# Callisto_Teknic_MSOx4_LSx3_v1p0.net
KiCad netlist of a schematic drawn in EAGLE
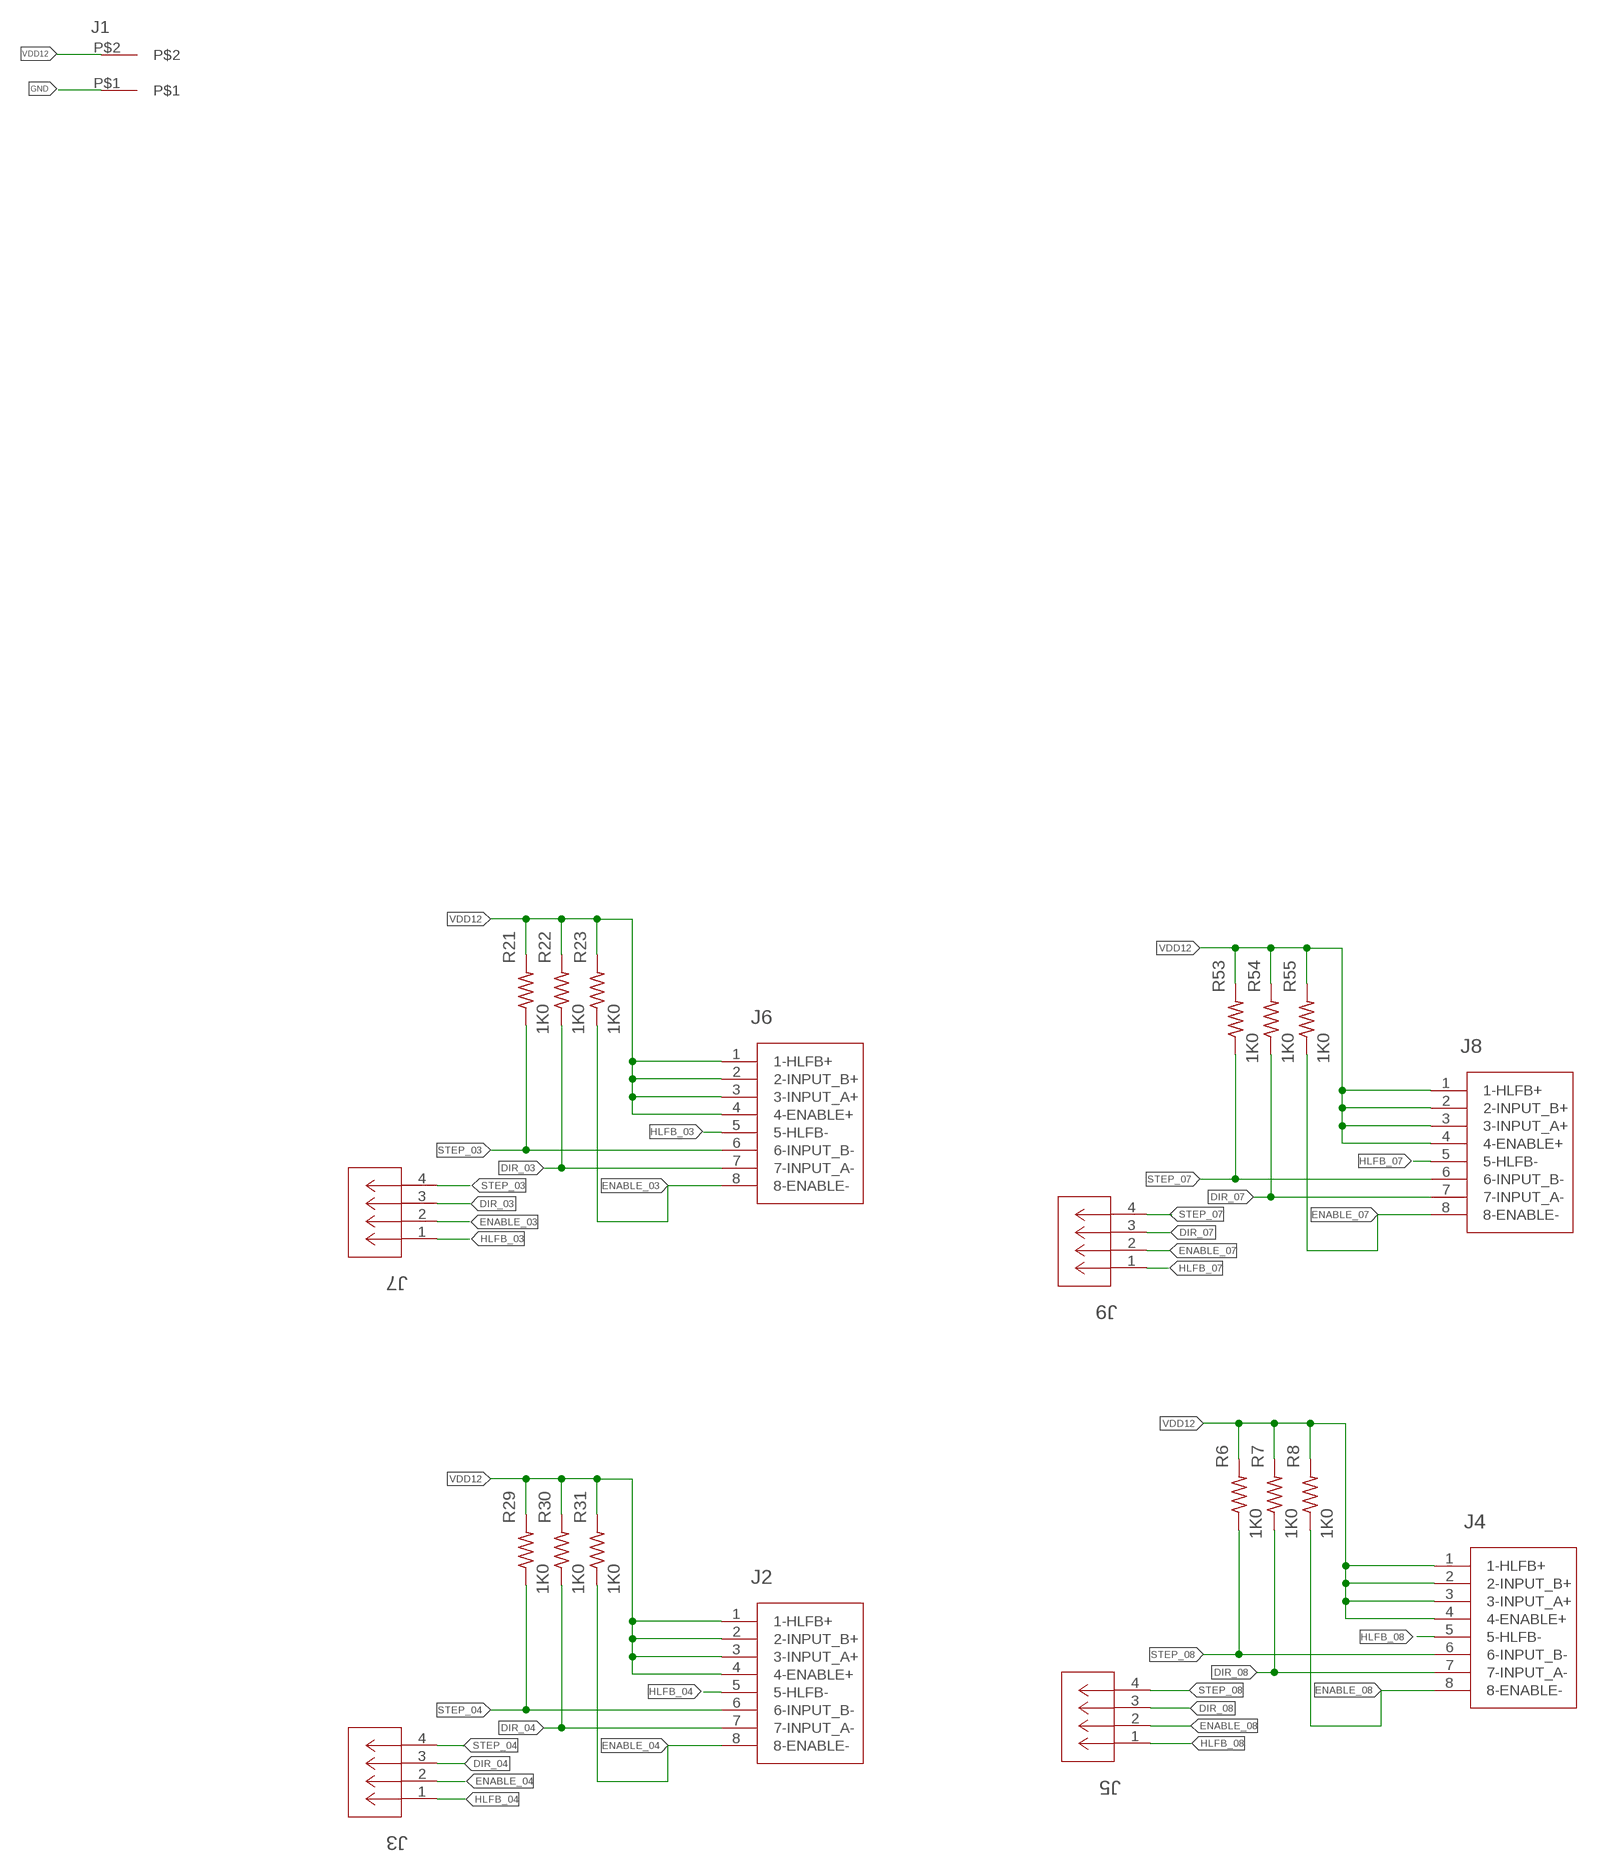
[diagram p0: schematic, sheet 1]

(export (version "E")
  (design (tool "Eeschema 10.0.6"))
  (components
    (comp (ref "J1")
      (value "2-pos")
      (footprint "eagle-import:2_3.81MM_PITCH")
      (fields (field (name "PARTNO") "691322310002"))
      (libsource (lib "eagle-import") (part "3.81MM_1_X_2_RT_ANGLE_PLUG_HEADER"))
    )
    (comp (ref "J2")
      (value "TEKNIC_8PIN_MOTOR")
      (footprint "eagle-import:CON_39281083")
      (fields
        (field (name "MANUFACTURER_PART_NUMBER") "39281083")
        (field (name "COPYRIGHT") "Copyright (C) 2022 Ultra Librarian. All rights reserved.")
      )
      (libsource (lib "eagle-import") (part "TEKNIC_8PIN_MOTOR"))
    )
    (comp (ref "J3")
      (value "CONN_530470410_PICOBLADE_X_4")
      (footprint "eagle-import:CON_530470410_MOL")
      (fields
        (field (name "MANUFACTURER_PART_NUMBER") "530470410")
        (field (name "COPYRIGHT") "Copyright (C) 2022 Ultra Librarian. All rights reserved.")
      )
      (libsource (lib "eagle-import") (part "CONN_530470410_PICOBLADE_X_4"))
    )
    (comp (ref "J4")
      (value "TEKNIC_8PIN_MOTOR")
      (footprint "eagle-import:CON_39281083")
      (fields
        (field (name "MANUFACTURER_PART_NUMBER") "39281083")
        (field (name "COPYRIGHT") "Copyright (C) 2022 Ultra Librarian. All rights reserved.")
      )
      (libsource (lib "eagle-import") (part "TEKNIC_8PIN_MOTOR"))
    )
    (comp (ref "J5")
      (value "CONN_530470410_PICOBLADE_X_4")
      (footprint "eagle-import:CON_530470410_MOL")
      (fields
        (field (name "MANUFACTURER_PART_NUMBER") "530470410")
        (field (name "COPYRIGHT") "Copyright (C) 2022 Ultra Librarian. All rights reserved.")
      )
      (libsource (lib "eagle-import") (part "CONN_530470410_PICOBLADE_X_4"))
    )
    (comp (ref "J6")
      (value "TEKNIC_8PIN_MOTOR")
      (footprint "eagle-import:CON_39281083")
      (fields
        (field (name "MANUFACTURER_PART_NUMBER") "39281083")
        (field (name "COPYRIGHT") "Copyright (C) 2022 Ultra Librarian. All rights reserved.")
      )
      (libsource (lib "eagle-import") (part "TEKNIC_8PIN_MOTOR"))
    )
    (comp (ref "J7")
      (value "CONN_530470410_PICOBLADE_X_4")
      (footprint "eagle-import:CON_530470410_MOL")
      (fields
        (field (name "MANUFACTURER_PART_NUMBER") "530470410")
        (field (name "COPYRIGHT") "Copyright (C) 2022 Ultra Librarian. All rights reserved.")
      )
      (libsource (lib "eagle-import") (part "CONN_530470410_PICOBLADE_X_4"))
    )
    (comp (ref "J8")
      (value "TEKNIC_8PIN_MOTOR")
      (footprint "eagle-import:CON_39281083")
      (fields
        (field (name "MANUFACTURER_PART_NUMBER") "39281083")
        (field (name "COPYRIGHT") "Copyright (C) 2022 Ultra Librarian. All rights reserved.")
      )
      (libsource (lib "eagle-import") (part "TEKNIC_8PIN_MOTOR"))
    )
    (comp (ref "J9")
      (value "CONN_530470410_PICOBLADE_X_4")
      (footprint "eagle-import:CON_530470410_MOL")
      (fields
        (field (name "MANUFACTURER_PART_NUMBER") "530470410")
        (field (name "COPYRIGHT") "Copyright (C) 2022 Ultra Librarian. All rights reserved.")
      )
      (libsource (lib "eagle-import") (part "CONN_530470410_PICOBLADE_X_4"))
    )
    (comp (ref "R6")
      (value "1K0")
      (footprint "eagle-import:0402")
      (fields (field (name "PARTNO") "CRG0402J1K0"))
      (libsource (lib "eagle-import") (part "R_0402_1K0"))
    )
    (comp (ref "R7")
      (value "1K0")
      (footprint "eagle-import:0402")
      (fields (field (name "PARTNO") "CRG0402J1K0"))
      (libsource (lib "eagle-import") (part "R_0402_1K0"))
    )
    (comp (ref "R8")
      (value "1K0")
      (footprint "eagle-import:0402")
      (fields (field (name "PARTNO") "CRG0402J1K0"))
      (libsource (lib "eagle-import") (part "R_0402_1K0"))
    )
    (comp (ref "R21")
      (value "1K0")
      (footprint "eagle-import:0402")
      (fields (field (name "PARTNO") "CRG0402J1K0"))
      (libsource (lib "eagle-import") (part "R_0402_1K0"))
    )
    (comp (ref "R22")
      (value "1K0")
      (footprint "eagle-import:0402")
      (fields (field (name "PARTNO") "CRG0402J1K0"))
      (libsource (lib "eagle-import") (part "R_0402_1K0"))
    )
    (comp (ref "R23")
      (value "1K0")
      (footprint "eagle-import:0402")
      (fields (field (name "PARTNO") "CRG0402J1K0"))
      (libsource (lib "eagle-import") (part "R_0402_1K0"))
    )
    (comp (ref "R29")
      (value "1K0")
      (footprint "eagle-import:0402")
      (fields (field (name "PARTNO") "CRG0402J1K0"))
      (libsource (lib "eagle-import") (part "R_0402_1K0"))
    )
    (comp (ref "R30")
      (value "1K0")
      (footprint "eagle-import:0402")
      (fields (field (name "PARTNO") "CRG0402J1K0"))
      (libsource (lib "eagle-import") (part "R_0402_1K0"))
    )
    (comp (ref "R31")
      (value "1K0")
      (footprint "eagle-import:0402")
      (fields (field (name "PARTNO") "CRG0402J1K0"))
      (libsource (lib "eagle-import") (part "R_0402_1K0"))
    )
    (comp (ref "R53")
      (value "1K0")
      (footprint "eagle-import:0402")
      (fields (field (name "PARTNO") "CRG0402J1K0"))
      (libsource (lib "eagle-import") (part "R_0402_1K0"))
    )
    (comp (ref "R54")
      (value "1K0")
      (footprint "eagle-import:0402")
      (fields (field (name "PARTNO") "CRG0402J1K0"))
      (libsource (lib "eagle-import") (part "R_0402_1K0"))
    )
    (comp (ref "R55")
      (value "1K0")
      (footprint "eagle-import:0402")
      (fields (field (name "PARTNO") "CRG0402J1K0"))
      (libsource (lib "eagle-import") (part "R_0402_1K0"))
    )
  )
  (nets
    (net (code "1") (name "DIR_03") (class "Default")
      (node (ref "J6") (pin "7") (pinfunction "7-INPUT_A-_7") (pintype "passive"))
      (node (ref "J7") (pin "3") (pinfunction "3_3") (pintype "passive"))
      (node (ref "R22") (pin "1") (pinfunction "1_1") (pintype "passive"))
    )
    (net (code "2") (name "DIR_04") (class "Default")
      (node (ref "J2") (pin "7") (pinfunction "7-INPUT_A-_7") (pintype "passive"))
      (node (ref "J3") (pin "3") (pinfunction "3_3") (pintype "passive"))
      (node (ref "R30") (pin "1") (pinfunction "1_1") (pintype "passive"))
    )
    (net (code "3") (name "DIR_07") (class "Default")
      (node (ref "J8") (pin "7") (pinfunction "7-INPUT_A-_7") (pintype "passive"))
      (node (ref "J9") (pin "3") (pinfunction "3_3") (pintype "passive"))
      (node (ref "R54") (pin "1") (pinfunction "1_1") (pintype "passive"))
    )
    (net (code "4") (name "DIR_08") (class "Default")
      (node (ref "J4") (pin "7") (pinfunction "7-INPUT_A-_7") (pintype "passive"))
      (node (ref "J5") (pin "3") (pinfunction "3_3") (pintype "passive"))
      (node (ref "R7") (pin "1") (pinfunction "1_1") (pintype "passive"))
    )
    (net (code "5") (name "ENABLE_03") (class "Default")
      (node (ref "J6") (pin "8") (pinfunction "8-ENABLE-_8") (pintype "passive"))
      (node (ref "J7") (pin "2") (pinfunction "2_2") (pintype "passive"))
      (node (ref "R23") (pin "1") (pinfunction "1_1") (pintype "passive"))
    )
    (net (code "6") (name "ENABLE_04") (class "Default")
      (node (ref "J2") (pin "8") (pinfunction "8-ENABLE-_8") (pintype "passive"))
      (node (ref "J3") (pin "2") (pinfunction "2_2") (pintype "passive"))
      (node (ref "R31") (pin "1") (pinfunction "1_1") (pintype "passive"))
    )
    (net (code "7") (name "ENABLE_07") (class "Default")
      (node (ref "J8") (pin "8") (pinfunction "8-ENABLE-_8") (pintype "passive"))
      (node (ref "J9") (pin "2") (pinfunction "2_2") (pintype "passive"))
      (node (ref "R55") (pin "1") (pinfunction "1_1") (pintype "passive"))
    )
    (net (code "8") (name "ENABLE_08") (class "Default")
      (node (ref "J4") (pin "8") (pinfunction "8-ENABLE-_8") (pintype "passive"))
      (node (ref "J5") (pin "2") (pinfunction "2_2") (pintype "passive"))
      (node (ref "R8") (pin "1") (pinfunction "1_1") (pintype "passive"))
    )
    (net (code "9") (name "GND") (class "Default")
      (node (ref "J1") (pin "P$1") (pinfunction "P$1_P$1") (pintype "bidirectional"))
    )
    (net (code "10") (name "HLFB_03") (class "Default")
      (node (ref "J6") (pin "5") (pinfunction "5-HLFB-_5") (pintype "passive"))
      (node (ref "J7") (pin "1") (pinfunction "1_1") (pintype "passive"))
    )
    (net (code "11") (name "HLFB_04") (class "Default")
      (node (ref "J2") (pin "5") (pinfunction "5-HLFB-_5") (pintype "passive"))
      (node (ref "J3") (pin "1") (pinfunction "1_1") (pintype "passive"))
    )
    (net (code "12") (name "HLFB_07") (class "Default")
      (node (ref "J8") (pin "5") (pinfunction "5-HLFB-_5") (pintype "passive"))
      (node (ref "J9") (pin "1") (pinfunction "1_1") (pintype "passive"))
    )
    (net (code "13") (name "HLFB_08") (class "Default")
      (node (ref "J4") (pin "5") (pinfunction "5-HLFB-_5") (pintype "passive"))
      (node (ref "J5") (pin "1") (pinfunction "1_1") (pintype "passive"))
    )
    (net (code "14") (name "STEP_03") (class "Default")
      (node (ref "J6") (pin "6") (pinfunction "6-INPUT_B-_6") (pintype "passive"))
      (node (ref "J7") (pin "4") (pinfunction "4_4") (pintype "passive"))
      (node (ref "R21") (pin "1") (pinfunction "1_1") (pintype "passive"))
    )
    (net (code "15") (name "STEP_04") (class "Default")
      (node (ref "J2") (pin "6") (pinfunction "6-INPUT_B-_6") (pintype "passive"))
      (node (ref "J3") (pin "4") (pinfunction "4_4") (pintype "passive"))
      (node (ref "R29") (pin "1") (pinfunction "1_1") (pintype "passive"))
    )
    (net (code "16") (name "STEP_07") (class "Default")
      (node (ref "J8") (pin "6") (pinfunction "6-INPUT_B-_6") (pintype "passive"))
      (node (ref "J9") (pin "4") (pinfunction "4_4") (pintype "passive"))
      (node (ref "R53") (pin "1") (pinfunction "1_1") (pintype "passive"))
    )
    (net (code "17") (name "STEP_08") (class "Default")
      (node (ref "J4") (pin "6") (pinfunction "6-INPUT_B-_6") (pintype "passive"))
      (node (ref "J5") (pin "4") (pinfunction "4_4") (pintype "passive"))
      (node (ref "R6") (pin "1") (pinfunction "1_1") (pintype "passive"))
    )
    (net (code "18") (name "VDD12") (class "Default")
      (node (ref "J1") (pin "P$2") (pinfunction "P$2_P$2") (pintype "bidirectional"))
      (node (ref "J2") (pin "1") (pinfunction "1-HLFB+_1") (pintype "passive"))
      (node (ref "J2") (pin "2") (pinfunction "2-INPUT_B+_2") (pintype "passive"))
      (node (ref "J2") (pin "3") (pinfunction "3-INPUT_A+_3") (pintype "passive"))
      (node (ref "J2") (pin "4") (pinfunction "4-ENABLE+_4") (pintype "passive"))
      (node (ref "J4") (pin "1") (pinfunction "1-HLFB+_1") (pintype "passive"))
      (node (ref "J4") (pin "2") (pinfunction "2-INPUT_B+_2") (pintype "passive"))
      (node (ref "J4") (pin "3") (pinfunction "3-INPUT_A+_3") (pintype "passive"))
      (node (ref "J4") (pin "4") (pinfunction "4-ENABLE+_4") (pintype "passive"))
      (node (ref "J6") (pin "1") (pinfunction "1-HLFB+_1") (pintype "passive"))
      (node (ref "J6") (pin "2") (pinfunction "2-INPUT_B+_2") (pintype "passive"))
      (node (ref "J6") (pin "3") (pinfunction "3-INPUT_A+_3") (pintype "passive"))
      (node (ref "J6") (pin "4") (pinfunction "4-ENABLE+_4") (pintype "passive"))
      (node (ref "J8") (pin "1") (pinfunction "1-HLFB+_1") (pintype "passive"))
      (node (ref "J8") (pin "2") (pinfunction "2-INPUT_B+_2") (pintype "passive"))
      (node (ref "J8") (pin "3") (pinfunction "3-INPUT_A+_3") (pintype "passive"))
      (node (ref "J8") (pin "4") (pinfunction "4-ENABLE+_4") (pintype "passive"))
      (node (ref "R21") (pin "2") (pinfunction "2_2") (pintype "passive"))
      (node (ref "R22") (pin "2") (pinfunction "2_2") (pintype "passive"))
      (node (ref "R23") (pin "2") (pinfunction "2_2") (pintype "passive"))
      (node (ref "R29") (pin "2") (pinfunction "2_2") (pintype "passive"))
      (node (ref "R30") (pin "2") (pinfunction "2_2") (pintype "passive"))
      (node (ref "R31") (pin "2") (pinfunction "2_2") (pintype "passive"))
      (node (ref "R53") (pin "2") (pinfunction "2_2") (pintype "passive"))
      (node (ref "R54") (pin "2") (pinfunction "2_2") (pintype "passive"))
      (node (ref "R55") (pin "2") (pinfunction "2_2") (pintype "passive"))
      (node (ref "R6") (pin "2") (pinfunction "2_2") (pintype "passive"))
      (node (ref "R7") (pin "2") (pinfunction "2_2") (pintype "passive"))
      (node (ref "R8") (pin "2") (pinfunction "2_2") (pintype "passive"))
    )
  )
)
